# PolarGraph.net
KiCad netlist of a schematic drawn in Altium Designer
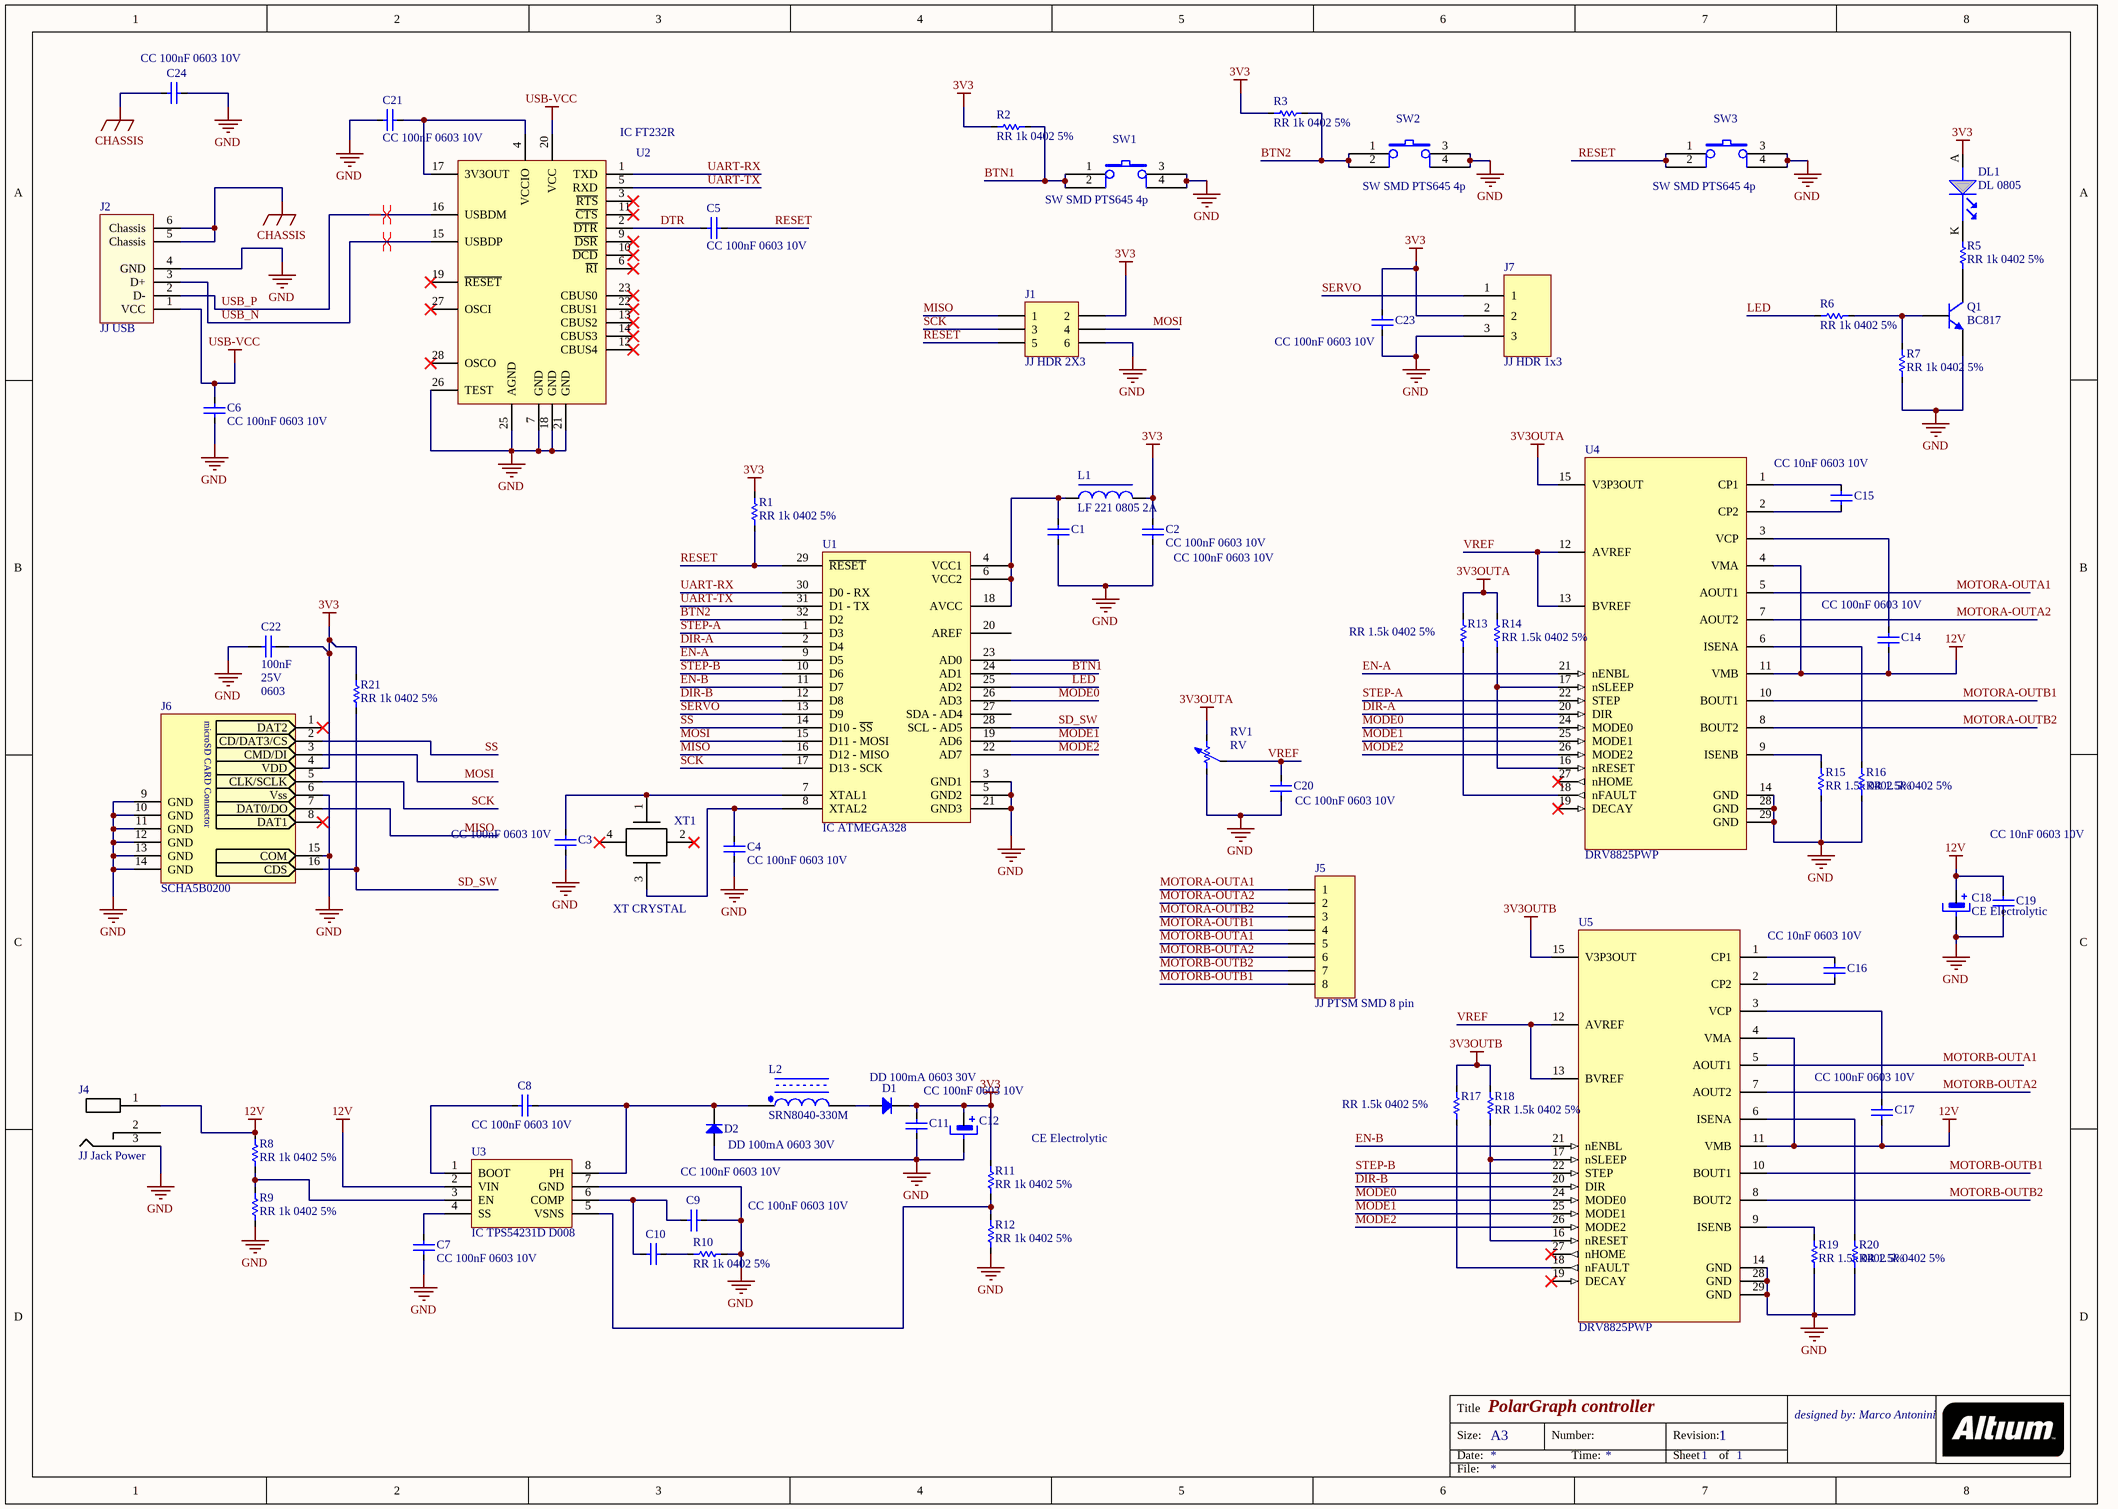
[diagram p0: PolarGraph.SchDoc]

(export (version "E")
  (design (tool "Eeschema 10.0.6"))
  (components
    (comp (ref "C1")
      (value "CC 100nF 0603 10V")
      (footprint "CC 0603 (1608 metric)")
      (description "Capacitor, Multi Layer Ceramic")
      (libsource (lib "ACME") (part "CC Ceramic"))
    )
    (comp (ref "C2")
      (value "CC 100nF 0603 10V")
      (footprint "CC 0603 (1608 metric)")
      (description "Capacitor, Multi Layer Ceramic")
      (libsource (lib "ACME") (part "CC Ceramic"))
    )
    (comp (ref "C3")
      (value "CC 100nF 0603 10V")
      (footprint "CC 0603 (1608 metric)")
      (description "Capacitor, Multi Layer Ceramic")
      (libsource (lib "ACME") (part "CC Ceramic"))
    )
    (comp (ref "C4")
      (value "CC 100nF 0603 10V")
      (footprint "CC 0603 (1608 metric)")
      (description "Capacitor, Multi Layer Ceramic")
      (libsource (lib "ACME") (part "CC Ceramic"))
    )
    (comp (ref "C5")
      (value "CC 100nF 0603 10V")
      (footprint "CC 0603 (1608 metric)")
      (description "Capacitor, Multi Layer Ceramic")
      (libsource (lib "ACME") (part "CC Ceramic"))
    )
    (comp (ref "C6")
      (value "CC 100nF 0603 10V")
      (footprint "CC 0603 (1608 metric)")
      (description "Capacitor, Multi Layer Ceramic")
      (libsource (lib "ACME") (part "CC Ceramic"))
    )
    (comp (ref "C7")
      (value "CC 100nF 0603 10V")
      (footprint "CC 0603 (1608 metric)")
      (description "Capacitor, Multi Layer Ceramic")
      (libsource (lib "ACME") (part "CC Ceramic"))
    )
    (comp (ref "C8")
      (value "CC 100nF 0603 10V")
      (footprint "CC 0603 (1608 metric)")
      (description "Capacitor, Multi Layer Ceramic")
      (libsource (lib "ACME") (part "CC Ceramic"))
    )
    (comp (ref "C9")
      (value "CC 100nF 0603 10V")
      (footprint "CC 0603 (1608 metric)")
      (description "Capacitor, Multi Layer Ceramic")
      (libsource (lib "ACME") (part "CC Ceramic"))
    )
    (comp (ref "C10")
      (value "CC 100nF 0603 10V")
      (footprint "CC 0603 (1608 metric)")
      (description "Capacitor, Multi Layer Ceramic")
      (libsource (lib "ACME") (part "CC Ceramic"))
    )
    (comp (ref "C11")
      (value "CC 100nF 0603 10V")
      (footprint "CC 0805 (2012 metric)")
      (description "Capacitor, Multi Layer Ceramic")
      (libsource (lib "ACME") (part "CC Ceramic"))
    )
    (comp (ref "C12")
      (value "CE Electrolytic")
      (footprint "CE 5.3x5.3x5.4")
      (description "Electrolytic Capacittor")
      (libsource (lib "ACME") (part "CE Electrolytic"))
    )
    (comp (ref "C14")
      (value "CC 100nF 0603 10V")
      (footprint "CC 0603 (1608 metric)")
      (description "Capacitor, Multi Layer Ceramic")
      (libsource (lib "ACME") (part "CC Ceramic"))
    )
    (comp (ref "C15")
      (value "CC 10nF 0603 10V")
      (footprint "CC 0603 (1608 metric)")
      (description "Capacitor, Multi Layer Ceramic")
      (libsource (lib "ACME") (part "CC Ceramic"))
    )
    (comp (ref "C16")
      (value "CC 10nF 0603 10V")
      (footprint "CC 0603 (1608 metric)")
      (description "Capacitor, Multi Layer Ceramic")
      (libsource (lib "ACME") (part "CC Ceramic"))
    )
    (comp (ref "C17")
      (value "CC 100nF 0603 10V")
      (footprint "CC 0603 (1608 metric)")
      (description "Capacitor, Multi Layer Ceramic")
      (libsource (lib "ACME") (part "CC Ceramic"))
    )
    (comp (ref "C18")
      (value "CE Electrolytic")
      (footprint "CE 6.6x6.6x5.4")
      (description "Electrolytic Capacittor")
      (libsource (lib "ACME") (part "CE Electrolytic"))
    )
    (comp (ref "C19")
      (value "CC 10nF 0603 10V")
      (footprint "CC 0805 (2012 metric)")
      (description "Capacitor, Multi Layer Ceramic")
      (libsource (lib "ACME") (part "CC Ceramic"))
    )
    (comp (ref "C20")
      (value "CC 100nF 0603 10V")
      (footprint "CC 0603 (1608 metric)")
      (description "Capacitor, Multi Layer Ceramic")
      (libsource (lib "ACME") (part "CC Ceramic"))
    )
    (comp (ref "C21")
      (value "CC 100nF 0603 10V")
      (footprint "CC 0603 (1608 metric)")
      (description "Capacitor, Multi Layer Ceramic")
      (libsource (lib "ACME") (part "CC Ceramic"))
    )
    (comp (ref "C22")
      (value "100nF")
      (footprint "0603_C")
      (description "Capacitor 0603, 100nF X7R 25V")
      (fields
        (field (name "VOLTAGE") "25V")
        (field (name "PACKAGE") "0603")
        (field (name "PART NUMBER") "C100nF-P0603-25V-X7R")
        (field (name "Comment") "Cap")
      )
      (libsource (lib "CROCO_DBLIB") (part "Cap"))
    )
    (comp (ref "C23")
      (value "CC 100nF 0603 10V")
      (footprint "CC 0805 (2012 metric)")
      (description "Capacitor, Multi Layer Ceramic")
      (libsource (lib "ACME") (part "CC Ceramic"))
    )
    (comp (ref "C24")
      (value "CC 100nF 0603 10V")
      (footprint "CC 1808 (4520 metric)")
      (description "Capacitor, Multi Layer Ceramic")
      (libsource (lib "ACME") (part "CC Ceramic"))
    )
    (comp (ref "D1")
      (value "DD 100mA 0603 30V")
      (footprint "DD SMA + SMB")
      (description "Normal Diode")
      (fields (field (name "PUBLISHER") "Altium Limited"))
      (libsource (lib "ACME") (part "DD Diode"))
    )
    (comp (ref "D2")
      (value "DD 100mA 0603 30V")
      (footprint "DD SMA + SMB")
      (description "Normal Diode")
      (fields (field (name "PUBLISHER") "Altium Limited"))
      (libsource (lib "ACME") (part "DD Diode"))
    )
    (comp (ref "DL1")
      (value "DL 0805")
      (footprint "LED 0805 - RED")
      (description "LED Diode 0805")
      (libsource (lib "Madefree") (part "DL Diode Led"))
    )
    (comp (ref "J1")
      (value "JJ HDR 2X3")
      (footprint "HDR 2X3")
      (libsource (lib "Madefree") (part "JJ HDR 2X3"))
    )
    (comp (ref "J2")
      (value "JJ USB")
      (footprint "USB Type B")
      (description "USB Socket")
      (libsource (lib "Madefree") (part "JJ USB"))
    )
    (comp (ref "J4")
      (value "JJ Jack Power")
      (footprint "JACK POWER")
      (libsource (lib "Madefree") (part "JJ Jack Power"))
    )
    (comp (ref "J5")
      (value "JJ PTSM SMD 8 pin")
      (footprint "PTSM 0,5/ 8-2,5-H SMD")
      (description "Terminal Block 8 pin")
      (fields (field (name "PUBLISHER") "Acme Systems"))
      (libsource (lib "Madefree") (part "JJ PTSM SMD 8 pin"))
    )
    (comp (ref "J6")
      (value "SCHA5B0200")
      (footprint "ALPS_SCHA5B0200")
      (description "microSD Card Connector (Push-push Type) SCHA Series")
      (fields (field (name "MANUFACTURER") "ALPS"))
      (libsource (lib "CROCO_DBLIB") (part "ALPS_SCHA5B0200"))
    )
    (comp (ref "J7")
      (value "JJ HDR 1x3")
      (footprint "HDR 1x3")
      (libsource (lib "Madefree") (part "JJ HDR 1x3"))
    )
    (comp (ref "L1")
      (value "LF 221 0805 2A")
      (footprint "LL 0603 (1608 metric)")
      (description "Ferrite 220 Ohm 2A 0805")
      (libsource (lib "ACME") (part "LF Ferrite"))
    )
    (comp (ref "L2")
      (value "SRN8040-330M")
      (footprint "INDC8080X400N")
      (description "Semi-shielded Power Inductors 33uH")
      (fields (field (name "MANUFACTURER") "Bourns"))
      (libsource (lib "CROCO_DBLIB") (part "INDUCTOR_SH"))
    )
    (comp (ref "Q1") (value "BC817") (footprint "SOT23_3") (libsource (lib "Madefree") (part "BC817")))
    (comp (ref "R1")
      (value "RR 1k 0402 5%")
      (footprint "RR 0603 (1608 metric)")
      (description "Resistor")
      (fields (field (name "PUBLISHER") "ACME Systems"))
      (libsource (lib "ACME") (part "RR Resistor"))
    )
    (comp (ref "R2")
      (value "RR 1k 0402 5%")
      (footprint "RR 0603 (1608 metric)")
      (description "Resistor")
      (fields (field (name "PUBLISHER") "ACME Systems"))
      (libsource (lib "ACME") (part "RR Resistor"))
    )
    (comp (ref "R3")
      (value "RR 1k 0402 5%")
      (footprint "RR 0603 (1608 metric)")
      (description "Resistor")
      (fields (field (name "PUBLISHER") "ACME Systems"))
      (libsource (lib "ACME") (part "RR Resistor"))
    )
    (comp (ref "R5")
      (value "RR 1k 0402 5%")
      (footprint "RR 0603 (1608 metric)")
      (description "Resistor")
      (fields (field (name "PUBLISHER") "ACME Systems"))
      (libsource (lib "ACME") (part "RR Resistor"))
    )
    (comp (ref "R6")
      (value "RR 1k 0402 5%")
      (footprint "RR 0603 (1608 metric)")
      (description "Resistor")
      (fields (field (name "PUBLISHER") "ACME Systems"))
      (libsource (lib "ACME") (part "RR Resistor"))
    )
    (comp (ref "R7")
      (value "RR 1k 0402 5%")
      (footprint "RR 0603 (1608 metric)")
      (description "Resistor")
      (fields (field (name "PUBLISHER") "ACME Systems"))
      (libsource (lib "ACME") (part "RR Resistor"))
    )
    (comp (ref "R8")
      (value "RR 1k 0402 5%")
      (footprint "RR 0603 (1608 metric)")
      (description "Resistor")
      (fields (field (name "PUBLISHER") "ACME Systems"))
      (libsource (lib "ACME") (part "RR Resistor"))
    )
    (comp (ref "R9")
      (value "RR 1k 0402 5%")
      (footprint "RR 0603 (1608 metric)")
      (description "Resistor")
      (fields (field (name "PUBLISHER") "ACME Systems"))
      (libsource (lib "ACME") (part "RR Resistor"))
    )
    (comp (ref "R10")
      (value "RR 1k 0402 5%")
      (footprint "RR 0603 (1608 metric)")
      (description "Resistor")
      (fields (field (name "PUBLISHER") "ACME Systems"))
      (libsource (lib "ACME") (part "RR Resistor"))
    )
    (comp (ref "R11")
      (value "RR 1k 0402 5%")
      (footprint "RR 0603 (1608 metric)")
      (description "Resistor")
      (fields (field (name "PUBLISHER") "ACME Systems"))
      (libsource (lib "ACME") (part "RR Resistor"))
    )
    (comp (ref "R12")
      (value "RR 1k 0402 5%")
      (footprint "RR 0603 (1608 metric)")
      (description "Resistor")
      (fields (field (name "PUBLISHER") "ACME Systems"))
      (libsource (lib "ACME") (part "RR Resistor"))
    )
    (comp (ref "R13")
      (value "RR 1.5k 0402 5%")
      (footprint "RR 0603 (1608 metric)")
      (description "Resistor")
      (fields (field (name "PUBLISHER") "ACME Systems"))
      (libsource (lib "ACME") (part "RR Resistor"))
    )
    (comp (ref "R14")
      (value "RR 1.5k 0402 5%")
      (footprint "RR 0603 (1608 metric)")
      (description "Resistor")
      (fields (field (name "PUBLISHER") "ACME Systems"))
      (libsource (lib "ACME") (part "RR Resistor"))
    )
    (comp (ref "R15")
      (value "RR 1.5k 0402 5%")
      (footprint "RR 0603 (1608 metric)")
      (description "Resistor")
      (fields (field (name "PUBLISHER") "ACME Systems"))
      (libsource (lib "ACME") (part "RR Resistor"))
    )
    (comp (ref "R16")
      (value "RR 1.5k 0402 5%")
      (footprint "RR 0603 (1608 metric)")
      (description "Resistor")
      (fields (field (name "PUBLISHER") "ACME Systems"))
      (libsource (lib "ACME") (part "RR Resistor"))
    )
    (comp (ref "R17")
      (value "RR 1.5k 0402 5%")
      (footprint "RR 0603 (1608 metric)")
      (description "Resistor")
      (fields (field (name "PUBLISHER") "ACME Systems"))
      (libsource (lib "ACME") (part "RR Resistor"))
    )
    (comp (ref "R18")
      (value "RR 1.5k 0402 5%")
      (footprint "RR 0603 (1608 metric)")
      (description "Resistor")
      (fields (field (name "PUBLISHER") "ACME Systems"))
      (libsource (lib "ACME") (part "RR Resistor"))
    )
    (comp (ref "R19")
      (value "RR 1.5k 0402 5%")
      (footprint "RR 0603 (1608 metric)")
      (description "Resistor")
      (fields (field (name "PUBLISHER") "ACME Systems"))
      (libsource (lib "ACME") (part "RR Resistor"))
    )
    (comp (ref "R20")
      (value "RR 1.5k 0402 5%")
      (footprint "RR 0603 (1608 metric)")
      (description "Resistor")
      (fields (field (name "PUBLISHER") "ACME Systems"))
      (libsource (lib "ACME") (part "RR Resistor"))
    )
    (comp (ref "R21")
      (value "RR 1k 0402 5%")
      (footprint "RR 0603 (1608 metric)")
      (description "Resistor")
      (fields (field (name "PUBLISHER") "ACME Systems"))
      (libsource (lib "ACME") (part "RR Resistor"))
    )
    (comp (ref "RV1")
      (value "RV")
      (footprint "RV ST-4EB")
      (description "Resistor")
      (fields (field (name "PUBLISHER") "ACME Systems"))
      (libsource (lib "ACME") (part "RV"))
    )
    (comp (ref "SW1")
      (value "SW SMD PTS645 4p")
      (footprint "Switch-4p PTS645")
      (description "Switch 4 pin PTS645")
      (libsource (lib "ACME") (part "SW SMD PTS645 4p"))
    )
    (comp (ref "SW2")
      (value "SW SMD PTS645 4p")
      (footprint "Switch-4p PTS645")
      (description "Switch 4 pin PTS645")
      (libsource (lib "ACME") (part "SW SMD PTS645 4p"))
    )
    (comp (ref "SW3")
      (value "SW SMD PTS645 4p")
      (footprint "Switch-4p PTS645")
      (description "Switch 4 pin PTS645")
      (libsource (lib "ACME") (part "SW SMD PTS645 4p"))
    )
    (comp (ref "U1")
      (value "IC ATMEGA328")
      (footprint "TQFP32")
      (libsource (lib "Madefree") (part "IC ATMEGA328"))
    )
    (comp (ref "U2")
      (value "IC FT232R")
      (footprint "SSOP28-FTDI")
      (description "The FT232BM is a USB to serial UART interface with the following advanced features")
      (libsource (lib "Madefree") (part "IC FT232R"))
    )
    (comp (ref "U3")
      (value "IC TPS54231D D008")
      (footprint "D008_M")
      (description "DC-DC converter TPS54231D D008")
      (fields (field (name "PUBLISHER") "Altium Limited"))
      (libsource (lib "ACME") (part "IC TPS54231D D008"))
    )
    (comp (ref "U4")
      (value "DRV8825PWP")
      (footprint "SOP65P640X120_HS-28N")
      (description "STEPPER MOTOR CONTROLLER IC")
      (fields (field (name "MANUFACTURER") "Texas Instrument"))
      (libsource (lib "CROCO_DBLIB") (part "DRV8825-28"))
    )
    (comp (ref "U5")
      (value "DRV8825PWP")
      (footprint "SOP65P640X120_HS-28N")
      (description "STEPPER MOTOR CONTROLLER IC")
      (fields (field (name "MANUFACTURER") "Texas Instrument"))
      (libsource (lib "CROCO_DBLIB") (part "DRV8825-28"))
    )
    (comp (ref "XT1")
      (value "XT CRYSTAL")
      (footprint "CRYSTAL 3.8x10.3")
      (libsource (lib "Madefree") (part "XT CRYSTAL"))
    )
  )
  (nets
    (net (code "1") (name "/BTN1") (class "Default")
      (node (ref "R2") (pin "1") (pinfunction "1_1") (pintype "passive"))
      (node (ref "SW1") (pin "1") (pinfunction "1_1") (pintype "passive"))
      (node (ref "SW1") (pin "2") (pinfunction "2_2") (pintype "passive"))
      (node (ref "U1") (pin "24") (pinfunction "AD1_24") (pintype "passive"))
    )
    (net (code "2") (name "/BTN2") (class "Default")
      (node (ref "R3") (pin "1") (pinfunction "1_1") (pintype "passive"))
      (node (ref "SW2") (pin "1") (pinfunction "1_1") (pintype "passive"))
      (node (ref "SW2") (pin "2") (pinfunction "2_2") (pintype "passive"))
      (node (ref "U1") (pin "32") (pinfunction "D2_32") (pintype "passive"))
    )
    (net (code "3") (name "/DIR-A") (class "Default")
      (node (ref "U1") (pin "2") (pinfunction "D4_2") (pintype "passive"))
      (node (ref "U4") (pin "20") (pinfunction "DIR_20") (pintype "input"))
    )
    (net (code "4") (name "/DIR-B") (class "Default")
      (node (ref "U1") (pin "12") (pinfunction "D8_12") (pintype "passive"))
      (node (ref "U5") (pin "20") (pinfunction "DIR_20") (pintype "input"))
    )
    (net (code "5") (name "/DTR") (class "Default")
      (node (ref "C5") (pin "1") (pinfunction "1_1") (pintype "passive"))
      (node (ref "U2") (pin "2") (pinfunction "~{DTR}_2") (pintype "passive"))
    )
    (net (code "6") (name "/EN-A") (class "Default")
      (node (ref "U1") (pin "9") (pinfunction "D5_9") (pintype "passive"))
      (node (ref "U4") (pin "21") (pinfunction "nENBL_21") (pintype "input"))
    )
    (net (code "7") (name "/EN-B") (class "Default")
      (node (ref "U1") (pin "11") (pinfunction "D7_11") (pintype "passive"))
      (node (ref "U5") (pin "21") (pinfunction "nENBL_21") (pintype "input"))
    )
    (net (code "8") (name "/LED") (class "Default")
      (node (ref "R6") (pin "1") (pinfunction "1_1") (pintype "passive"))
      (node (ref "U1") (pin "25") (pinfunction "AD2_25") (pintype "passive"))
    )
    (net (code "9") (name "/MISO") (class "Default")
      (node (ref "J1") (pin "1") (pinfunction "1_1") (pintype "passive"))
      (node (ref "J6") (pin "7") (pinfunction "DAT0/DO_7") (pintype "passive"))
      (node (ref "U1") (pin "16") (pinfunction "D12_-_MISO_16") (pintype "passive"))
    )
    (net (code "10") (name "/MODE0") (class "Default")
      (node (ref "U1") (pin "26") (pinfunction "AD3_26") (pintype "passive"))
      (node (ref "U4") (pin "24") (pinfunction "MODE0_24") (pintype "input"))
      (node (ref "U5") (pin "24") (pinfunction "MODE0_24") (pintype "input"))
    )
    (net (code "11") (name "/MODE1") (class "Default")
      (node (ref "U1") (pin "19") (pinfunction "AD6_19") (pintype "passive"))
      (node (ref "U4") (pin "25") (pinfunction "MODE1_25") (pintype "input"))
      (node (ref "U5") (pin "25") (pinfunction "MODE1_25") (pintype "input"))
    )
    (net (code "12") (name "/MODE2") (class "Default")
      (node (ref "U1") (pin "22") (pinfunction "AD7_22") (pintype "passive"))
      (node (ref "U4") (pin "26") (pinfunction "MODE2_26") (pintype "input"))
      (node (ref "U5") (pin "26") (pinfunction "MODE2_26") (pintype "input"))
    )
    (net (code "13") (name "/MOSI") (class "Default")
      (node (ref "J1") (pin "4") (pinfunction "4_4") (pintype "passive"))
      (node (ref "J6") (pin "3") (pinfunction "CMD/DI_3") (pintype "passive"))
      (node (ref "U1") (pin "15") (pinfunction "D11_-_MOSI_15") (pintype "passive"))
    )
    (net (code "14") (name "/MOTORA-OUTA1") (class "Default")
      (node (ref "J5") (pin "1") (pinfunction "1_1") (pintype "passive"))
      (node (ref "U4") (pin "5") (pinfunction "AOUT1_5") (pintype "passive"))
    )
    (net (code "15") (name "/MOTORA-OUTA2") (class "Default")
      (node (ref "J5") (pin "2") (pinfunction "2_2") (pintype "passive"))
      (node (ref "U4") (pin "7") (pinfunction "AOUT2_7") (pintype "passive"))
    )
    (net (code "16") (name "/MOTORA-OUTB1") (class "Default")
      (node (ref "J5") (pin "4") (pinfunction "4_4") (pintype "passive"))
      (node (ref "U4") (pin "10") (pinfunction "BOUT1_10") (pintype "passive"))
    )
    (net (code "17") (name "/MOTORA-OUTB2") (class "Default")
      (node (ref "J5") (pin "3") (pinfunction "3_3") (pintype "passive"))
      (node (ref "U4") (pin "8") (pinfunction "BOUT2_8") (pintype "passive"))
    )
    (net (code "18") (name "/MOTORB-OUTA1") (class "Default")
      (node (ref "J5") (pin "5") (pinfunction "5_5") (pintype "passive"))
      (node (ref "U5") (pin "5") (pinfunction "AOUT1_5") (pintype "passive"))
    )
    (net (code "19") (name "/MOTORB-OUTA2") (class "Default")
      (node (ref "J5") (pin "6") (pinfunction "6_6") (pintype "passive"))
      (node (ref "U5") (pin "7") (pinfunction "AOUT2_7") (pintype "passive"))
    )
    (net (code "20") (name "/MOTORB-OUTB1") (class "Default")
      (node (ref "J5") (pin "8") (pinfunction "8_8") (pintype "passive"))
      (node (ref "U5") (pin "10") (pinfunction "BOUT1_10") (pintype "passive"))
    )
    (net (code "21") (name "/MOTORB-OUTB2") (class "Default")
      (node (ref "J5") (pin "7") (pinfunction "7_7") (pintype "passive"))
      (node (ref "U5") (pin "8") (pinfunction "BOUT2_8") (pintype "passive"))
    )
    (net (code "22") (name "/RESET") (class "Default")
      (node (ref "C5") (pin "2") (pinfunction "2_2") (pintype "passive"))
      (node (ref "J1") (pin "5") (pinfunction "5_5") (pintype "passive"))
      (node (ref "R1") (pin "2") (pinfunction "2_2") (pintype "passive"))
      (node (ref "SW3") (pin "1") (pinfunction "1_1") (pintype "passive"))
      (node (ref "SW3") (pin "2") (pinfunction "2_2") (pintype "passive"))
      (node (ref "U1") (pin "29") (pinfunction "~{RESET}_29") (pintype "passive"))
    )
    (net (code "23") (name "/SCK") (class "Default")
      (node (ref "J1") (pin "3") (pinfunction "3_3") (pintype "passive"))
      (node (ref "J6") (pin "5") (pinfunction "CLK/SCLK_5") (pintype "passive"))
      (node (ref "U1") (pin "17") (pinfunction "D13_-_SCK_17") (pintype "passive"))
    )
    (net (code "24") (name "/SD_SW") (class "Default")
      (node (ref "J6") (pin "16") (pinfunction "CDS_16") (pintype "passive"))
      (node (ref "R21") (pin "2") (pinfunction "2_2") (pintype "passive"))
      (node (ref "U1") (pin "28") (pinfunction "SCL_-_AD5_28") (pintype "passive"))
    )
    (net (code "25") (name "/SERVO") (class "Default")
      (node (ref "J7") (pin "1") (pinfunction "1_1") (pintype "passive"))
      (node (ref "U1") (pin "13") (pinfunction "D9_13") (pintype "passive"))
    )
    (net (code "26") (name "/SS") (class "Default")
      (node (ref "J6") (pin "2") (pinfunction "CD/DAT3/CS_2") (pintype "passive"))
      (node (ref "U1") (pin "14") (pinfunction "D10_-_~{SS}_14") (pintype "passive"))
    )
    (net (code "27") (name "/STEP-A") (class "Default")
      (node (ref "U1") (pin "1") (pinfunction "D3_1") (pintype "passive"))
      (node (ref "U4") (pin "22") (pinfunction "STEP_22") (pintype "input"))
    )
    (net (code "28") (name "/STEP-B") (class "Default")
      (node (ref "U1") (pin "10") (pinfunction "D6_10") (pintype "passive"))
      (node (ref "U5") (pin "22") (pinfunction "STEP_22") (pintype "input"))
    )
    (net (code "29") (name "/UART-RX") (class "Default")
      (node (ref "U1") (pin "30") (pinfunction "D0_-_RX_30") (pintype "passive"))
      (node (ref "U2") (pin "1") (pinfunction "TXD_1") (pintype "passive"))
    )
    (net (code "30") (name "/UART-TX") (class "Default")
      (node (ref "U1") (pin "31") (pinfunction "D1_-_TX_31") (pintype "passive"))
      (node (ref "U2") (pin "5") (pinfunction "RXD_5") (pintype "passive"))
    )
    (net (code "31") (name "/USB_N") (class "Default")
      (node (ref "J2") (pin "3") (pinfunction "D+_3") (pintype "passive"))
      (node (ref "U2") (pin "15") (pinfunction "USBDP_15") (pintype "passive"))
    )
    (net (code "32") (name "/USB_P") (class "Default")
      (node (ref "J2") (pin "2") (pinfunction "D-_2") (pintype "passive"))
      (node (ref "U2") (pin "16") (pinfunction "USBDM_16") (pintype "passive"))
    )
    (net (code "33") (name "/VREF") (class "Default")
      (node (ref "C20") (pin "1") (pinfunction "1_1") (pintype "passive"))
      (node (ref "RV1") (pin "2") (pinfunction "2_2") (pintype "passive"))
      (node (ref "U4") (pin "12") (pinfunction "AVREF_12") (pintype "passive"))
      (node (ref "U4") (pin "13") (pinfunction "BVREF_13") (pintype "passive"))
      (node (ref "U5") (pin "12") (pinfunction "AVREF_12") (pintype "passive"))
      (node (ref "U5") (pin "13") (pinfunction "BVREF_13") (pintype "passive"))
    )
    (net (code "34") (name "3V3") (class "Default")
      (node (ref "C11") (pin "1") (pinfunction "1_1") (pintype "passive"))
      (node (ref "C12") (pin "1") (pinfunction "1_1") (pintype "passive"))
      (node (ref "C2") (pin "1") (pinfunction "1_1") (pintype "passive"))
      (node (ref "C22") (pin "2") (pinfunction "2_2") (pintype "passive"))
      (node (ref "C23") (pin "1") (pinfunction "1_1") (pintype "passive"))
      (node (ref "D1") (pin "K") (pinfunction "K_K") (pintype "passive"))
      (node (ref "DL1") (pin "A") (pinfunction "A_A") (pintype "passive"))
      (node (ref "J1") (pin "2") (pinfunction "2_2") (pintype "passive"))
      (node (ref "J6") (pin "4") (pinfunction "VDD_4") (pintype "passive"))
      (node (ref "J7") (pin "2") (pinfunction "2_2") (pintype "passive"))
      (node (ref "L1") (pin "2") (pinfunction "2_2") (pintype "passive"))
      (node (ref "R1") (pin "1") (pinfunction "1_1") (pintype "passive"))
      (node (ref "R11") (pin "2") (pinfunction "2_2") (pintype "passive"))
      (node (ref "R2") (pin "2") (pinfunction "2_2") (pintype "passive"))
      (node (ref "R21") (pin "1") (pinfunction "1_1") (pintype "passive"))
      (node (ref "R3") (pin "2") (pinfunction "2_2") (pintype "passive"))
    )
    (net (code "35") (name "3V3OUTA") (class "Default")
      (node (ref "R13") (pin "2") (pinfunction "2_2") (pintype "passive"))
      (node (ref "R14") (pin "2") (pinfunction "2_2") (pintype "passive"))
      (node (ref "RV1") (pin "3") (pinfunction "3_3") (pintype "passive"))
      (node (ref "U4") (pin "15") (pinfunction "V3P3OUT_15") (pintype "passive"))
    )
    (net (code "36") (name "3V3OUTB") (class "Default")
      (node (ref "R17") (pin "2") (pinfunction "2_2") (pintype "passive"))
      (node (ref "R18") (pin "2") (pinfunction "2_2") (pintype "passive"))
      (node (ref "U5") (pin "15") (pinfunction "V3P3OUT_15") (pintype "passive"))
    )
    (net (code "37") (name "12V") (class "Default")
      (node (ref "C14") (pin "1") (pinfunction "1_1") (pintype "passive"))
      (node (ref "C17") (pin "1") (pinfunction "1_1") (pintype "passive"))
      (node (ref "C18") (pin "1") (pinfunction "1_1") (pintype "passive"))
      (node (ref "C19") (pin "2") (pinfunction "2_2") (pintype "passive"))
      (node (ref "J4") (pin "1") (pinfunction "1_1") (pintype "passive"))
      (node (ref "R8") (pin "2") (pinfunction "2_2") (pintype "passive"))
      (node (ref "U3") (pin "2") (pinfunction "VIN_2") (pintype "passive"))
      (node (ref "U4") (pin "11") (pinfunction "VMB_11") (pintype "passive"))
      (node (ref "U4") (pin "4") (pinfunction "VMA_4") (pintype "passive"))
      (node (ref "U5") (pin "11") (pinfunction "VMB_11") (pintype "passive"))
      (node (ref "U5") (pin "4") (pinfunction "VMA_4") (pintype "passive"))
    )
    (net (code "38") (name "CHASSIS") (class "Default")
      (node (ref "C24") (pin "1") (pinfunction "1_1") (pintype "passive"))
      (node (ref "J2") (pin "5") (pinfunction "Chassis_5") (pintype "passive"))
      (node (ref "J2") (pin "6") (pinfunction "Chassis_6") (pintype "passive"))
    )
    (net (code "39") (name "GND") (class "Default")
      (node (ref "C1") (pin "2") (pinfunction "2_2") (pintype "passive"))
      (node (ref "C11") (pin "2") (pinfunction "2_2") (pintype "passive"))
      (node (ref "C12") (pin "2") (pinfunction "2_2") (pintype "passive"))
      (node (ref "C18") (pin "2") (pinfunction "2_2") (pintype "passive"))
      (node (ref "C19") (pin "1") (pinfunction "1_1") (pintype "passive"))
      (node (ref "C2") (pin "2") (pinfunction "2_2") (pintype "passive"))
      (node (ref "C20") (pin "2") (pinfunction "2_2") (pintype "passive"))
      (node (ref "C21") (pin "2") (pinfunction "2_2") (pintype "passive"))
      (node (ref "C22") (pin "1") (pinfunction "1_1") (pintype "passive"))
      (node (ref "C23") (pin "2") (pinfunction "2_2") (pintype "passive"))
      (node (ref "C24") (pin "2") (pinfunction "2_2") (pintype "passive"))
      (node (ref "C3") (pin "1") (pinfunction "1_1") (pintype "passive"))
      (node (ref "C4") (pin "1") (pinfunction "1_1") (pintype "passive"))
      (node (ref "C6") (pin "1") (pinfunction "1_1") (pintype "passive"))
      (node (ref "C7") (pin "2") (pinfunction "2_2") (pintype "passive"))
      (node (ref "C9") (pin "1") (pinfunction "1_1") (pintype "passive"))
      (node (ref "D2") (pin "A") (pinfunction "A_A") (pintype "passive"))
      (node (ref "J1") (pin "6") (pinfunction "6_6") (pintype "passive"))
      (node (ref "J2") (pin "4") (pinfunction "GND_4") (pintype "passive"))
      (node (ref "J4") (pin "3") (pinfunction "3_3") (pintype "passive"))
      (node (ref "J6") (pin "10") (pinfunction "GND_10") (pintype "passive"))
      (node (ref "J6") (pin "11") (pinfunction "GND_11") (pintype "passive"))
      (node (ref "J6") (pin "12") (pinfunction "GND_12") (pintype "passive"))
      (node (ref "J6") (pin "13") (pinfunction "GND_13") (pintype "passive"))
      (node (ref "J6") (pin "14") (pinfunction "GND_14") (pintype "passive"))
      (node (ref "J6") (pin "15") (pinfunction "COM_15") (pintype "passive"))
      (node (ref "J6") (pin "6") (pinfunction "Vss_6") (pintype "passive"))
      (node (ref "J6") (pin "9") (pinfunction "GND_9") (pintype "passive"))
      (node (ref "J7") (pin "3") (pinfunction "3_3") (pintype "passive"))
      (node (ref "Q1") (pin "2") (pinfunction "E_2") (pintype "passive"))
      (node (ref "R10") (pin "1") (pinfunction "1_1") (pintype "passive"))
      (node (ref "R12") (pin "1") (pinfunction "1_1") (pintype "passive"))
      (node (ref "R15") (pin "2") (pinfunction "2_2") (pintype "passive"))
      (node (ref "R16") (pin "2") (pinfunction "2_2") (pintype "passive"))
      (node (ref "R19") (pin "2") (pinfunction "2_2") (pintype "passive"))
      (node (ref "R20") (pin "2") (pinfunction "2_2") (pintype "passive"))
      (node (ref "R7") (pin "1") (pinfunction "1_1") (pintype "passive"))
      (node (ref "R9") (pin "1") (pinfunction "1_1") (pintype "passive"))
      (node (ref "RV1") (pin "1") (pinfunction "1_1") (pintype "passive"))
      (node (ref "SW1") (pin "3") (pinfunction "3_3") (pintype "passive"))
      (node (ref "SW1") (pin "4") (pinfunction "4_4") (pintype "passive"))
      (node (ref "SW2") (pin "3") (pinfunction "3_3") (pintype "passive"))
      (node (ref "SW2") (pin "4") (pinfunction "4_4") (pintype "passive"))
      (node (ref "SW3") (pin "3") (pinfunction "3_3") (pintype "passive"))
      (node (ref "SW3") (pin "4") (pinfunction "4_4") (pintype "passive"))
      (node (ref "U1") (pin "21") (pinfunction "GND3_21") (pintype "passive"))
      (node (ref "U1") (pin "3") (pinfunction "GND1_3") (pintype "passive"))
      (node (ref "U1") (pin "5") (pinfunction "GND2_5") (pintype "passive"))
      (node (ref "U2") (pin "18") (pinfunction "GND_18") (pintype "passive"))
      (node (ref "U2") (pin "21") (pinfunction "GND_21") (pintype "passive"))
      (node (ref "U2") (pin "25") (pinfunction "AGND_25") (pintype "passive"))
      (node (ref "U2") (pin "26") (pinfunction "TEST_26") (pintype "passive"))
      (node (ref "U2") (pin "7") (pinfunction "GND_7") (pintype "passive"))
      (node (ref "U3") (pin "7") (pinfunction "GND_7") (pintype "passive"))
      (node (ref "U4") (pin "14") (pinfunction "GND_14") (pintype "power_in"))
      (node (ref "U4") (pin "28") (pinfunction "GND_28") (pintype "power_in"))
      (node (ref "U4") (pin "29") (pinfunction "GND_29") (pintype "power_in"))
      (node (ref "U5") (pin "14") (pinfunction "GND_14") (pintype "power_in"))
      (node (ref "U5") (pin "28") (pinfunction "GND_28") (pintype "power_in"))
      (node (ref "U5") (pin "29") (pinfunction "GND_29") (pintype "power_in"))
    )
    (net (code "40") (name "Net-(C10-Pad1)") (class "Default")
      (node (ref "C10") (pin "1") (pinfunction "1_1") (pintype "passive"))
      (node (ref "R10") (pin "2") (pinfunction "2_2") (pintype "passive"))
    )
    (net (code "41") (name "Net-(D1-PadA)") (class "Default")
      (node (ref "D1") (pin "A") (pinfunction "A_A") (pintype "passive"))
      (node (ref "L2") (pin "2") (pinfunction "2_2") (pintype "passive"))
    )
    (net (code "42") (name "Net-(DL1-PadK)") (class "Default")
      (node (ref "DL1") (pin "K") (pinfunction "K_K") (pintype "passive"))
      (node (ref "R5") (pin "2") (pinfunction "2_2") (pintype "passive"))
    )
    (net (code "43") (name "Net-(Q1-B)") (class "Default")
      (node (ref "Q1") (pin "1") (pinfunction "B_1") (pintype "passive"))
      (node (ref "R6") (pin "2") (pinfunction "2_2") (pintype "passive"))
      (node (ref "R7") (pin "2") (pinfunction "2_2") (pintype "passive"))
    )
    (net (code "44") (name "Net-(Q1-C)") (class "Default")
      (node (ref "Q1") (pin "3") (pinfunction "C_3") (pintype "passive"))
      (node (ref "R5") (pin "1") (pinfunction "1_1") (pintype "passive"))
    )
    (net (code "45") (name "Net-(U1-AVCC)") (class "Default")
      (node (ref "C1") (pin "1") (pinfunction "1_1") (pintype "passive"))
      (node (ref "L1") (pin "1") (pinfunction "1_1") (pintype "passive"))
      (node (ref "U1") (pin "18") (pinfunction "AVCC_18") (pintype "passive"))
      (node (ref "U1") (pin "4") (pinfunction "VCC1_4") (pintype "passive"))
      (node (ref "U1") (pin "6") (pinfunction "VCC2_6") (pintype "passive"))
    )
    (net (code "46") (name "Net-(U1-XTAL1)") (class "Default")
      (node (ref "C3") (pin "2") (pinfunction "2_2") (pintype "passive"))
      (node (ref "U1") (pin "7") (pinfunction "XTAL1_7") (pintype "passive"))
      (node (ref "XT1") (pin "1") (pinfunction "X1_1") (pintype "passive"))
    )
    (net (code "47") (name "Net-(U1-XTAL2)") (class "Default")
      (node (ref "C4") (pin "2") (pinfunction "2_2") (pintype "passive"))
      (node (ref "U1") (pin "8") (pinfunction "XTAL2_8") (pintype "passive"))
      (node (ref "XT1") (pin "3") (pinfunction "X2_3") (pintype "passive"))
    )
    (net (code "48") (name "Net-(U2-3V3OUT)") (class "Default")
      (node (ref "C21") (pin "1") (pinfunction "1_1") (pintype "passive"))
      (node (ref "U2") (pin "17") (pinfunction "3V3OUT_17") (pintype "passive"))
      (node (ref "U2") (pin "4") (pinfunction "VCCIO_4") (pintype "passive"))
    )
    (net (code "49") (name "Net-(U3-BOOT)") (class "Default")
      (node (ref "C8") (pin "2") (pinfunction "2_2") (pintype "passive"))
      (node (ref "U3") (pin "1") (pinfunction "BOOT_1") (pintype "passive"))
    )
    (net (code "50") (name "Net-(U3-COMP)") (class "Default")
      (node (ref "C10") (pin "2") (pinfunction "2_2") (pintype "passive"))
      (node (ref "C9") (pin "2") (pinfunction "2_2") (pintype "passive"))
      (node (ref "U3") (pin "6") (pinfunction "COMP_6") (pintype "passive"))
    )
    (net (code "51") (name "Net-(U3-EN)") (class "Default")
      (node (ref "R8") (pin "1") (pinfunction "1_1") (pintype "passive"))
      (node (ref "R9") (pin "2") (pinfunction "2_2") (pintype "passive"))
      (node (ref "U3") (pin "3") (pinfunction "EN_3") (pintype "power_in"))
    )
    (net (code "52") (name "Net-(U3-PH)") (class "Default")
      (node (ref "C8") (pin "1") (pinfunction "1_1") (pintype "passive"))
      (node (ref "D2") (pin "K") (pinfunction "K_K") (pintype "passive"))
      (node (ref "L2") (pin "1") (pinfunction "1_1") (pintype "passive"))
      (node (ref "U3") (pin "8") (pinfunction "PH_8") (pintype "power_in"))
    )
    (net (code "53") (name "Net-(U3-SS)") (class "Default")
      (node (ref "C7") (pin "1") (pinfunction "1_1") (pintype "passive"))
      (node (ref "U3") (pin "4") (pinfunction "SS_4") (pintype "passive"))
    )
    (net (code "54") (name "Net-(U3-VSNS)") (class "Default")
      (node (ref "R11") (pin "1") (pinfunction "1_1") (pintype "passive"))
      (node (ref "R12") (pin "2") (pinfunction "2_2") (pintype "passive"))
      (node (ref "U3") (pin "5") (pinfunction "VSNS_5") (pintype "power_in"))
    )
    (net (code "55") (name "Net-(U4-CP1)") (class "Default")
      (node (ref "C15") (pin "2") (pinfunction "2_2") (pintype "passive"))
      (node (ref "U4") (pin "1") (pinfunction "CP1_1") (pintype "passive"))
    )
    (net (code "56") (name "Net-(U4-CP2)") (class "Default")
      (node (ref "C15") (pin "1") (pinfunction "1_1") (pintype "passive"))
      (node (ref "U4") (pin "2") (pinfunction "CP2_2") (pintype "passive"))
    )
    (net (code "57") (name "Net-(U4-ISENA)") (class "Default")
      (node (ref "R16") (pin "1") (pinfunction "1_1") (pintype "passive"))
      (node (ref "U4") (pin "6") (pinfunction "ISENA_6") (pintype "passive"))
    )
    (net (code "58") (name "Net-(U4-ISENB)") (class "Default")
      (node (ref "R15") (pin "1") (pinfunction "1_1") (pintype "passive"))
      (node (ref "U4") (pin "9") (pinfunction "ISENB_9") (pintype "passive"))
    )
    (net (code "59") (name "Net-(U4-VCP)") (class "Default")
      (node (ref "C14") (pin "2") (pinfunction "2_2") (pintype "passive"))
      (node (ref "U4") (pin "3") (pinfunction "VCP_3") (pintype "passive"))
    )
    (net (code "60") (name "Net-(U4-nFAULT)") (class "Default")
      (node (ref "R13") (pin "1") (pinfunction "1_1") (pintype "passive"))
      (node (ref "U4") (pin "18") (pinfunction "nFAULT_18") (pintype "output"))
    )
    (net (code "61") (name "Net-(U4-nRESET)") (class "Default")
      (node (ref "R14") (pin "1") (pinfunction "1_1") (pintype "passive"))
      (node (ref "U4") (pin "16") (pinfunction "nRESET_16") (pintype "input"))
      (node (ref "U4") (pin "17") (pinfunction "nSLEEP_17") (pintype "input"))
    )
    (net (code "62") (name "Net-(U5-CP1)") (class "Default")
      (node (ref "C16") (pin "2") (pinfunction "2_2") (pintype "passive"))
      (node (ref "U5") (pin "1") (pinfunction "CP1_1") (pintype "passive"))
    )
    (net (code "63") (name "Net-(U5-CP2)") (class "Default")
      (node (ref "C16") (pin "1") (pinfunction "1_1") (pintype "passive"))
      (node (ref "U5") (pin "2") (pinfunction "CP2_2") (pintype "passive"))
    )
    (net (code "64") (name "Net-(U5-ISENA)") (class "Default")
      (node (ref "R20") (pin "1") (pinfunction "1_1") (pintype "passive"))
      (node (ref "U5") (pin "6") (pinfunction "ISENA_6") (pintype "passive"))
    )
    (net (code "65") (name "Net-(U5-ISENB)") (class "Default")
      (node (ref "R19") (pin "1") (pinfunction "1_1") (pintype "passive"))
      (node (ref "U5") (pin "9") (pinfunction "ISENB_9") (pintype "passive"))
    )
    (net (code "66") (name "Net-(U5-VCP)") (class "Default")
      (node (ref "C17") (pin "2") (pinfunction "2_2") (pintype "passive"))
      (node (ref "U5") (pin "3") (pinfunction "VCP_3") (pintype "passive"))
    )
    (net (code "67") (name "Net-(U5-nFAULT)") (class "Default")
      (node (ref "R17") (pin "1") (pinfunction "1_1") (pintype "passive"))
      (node (ref "U5") (pin "18") (pinfunction "nFAULT_18") (pintype "output"))
    )
    (net (code "68") (name "Net-(U5-nRESET)") (class "Default")
      (node (ref "R18") (pin "1") (pinfunction "1_1") (pintype "passive"))
      (node (ref "U5") (pin "16") (pinfunction "nRESET_16") (pintype "input"))
      (node (ref "U5") (pin "17") (pinfunction "nSLEEP_17") (pintype "input"))
    )
    (net (code "69") (name "USB-VCC") (class "Default")
      (node (ref "C6") (pin "2") (pinfunction "2_2") (pintype "passive"))
      (node (ref "J2") (pin "1") (pinfunction "VCC_1") (pintype "passive"))
      (node (ref "U2") (pin "20") (pinfunction "VCC_20") (pintype "passive"))
    )
    (net (code "70") (name "unconnected-(J4-Pad2)") (class "Default")
      (node (ref "J4") (pin "2") (pinfunction "2_2") (pintype "passive"))
    )
    (net (code "71") (name "unconnected-(J6-DAT1-Pad8)") (class "Default")
      (node (ref "J6") (pin "8") (pinfunction "DAT1_8") (pintype "passive+no_connect"))
    )
    (net (code "72") (name "unconnected-(J6-DAT2-Pad1)") (class "Default")
      (node (ref "J6") (pin "1") (pinfunction "DAT2_1") (pintype "passive+no_connect"))
    )
    (net (code "73") (name "unconnected-(U1-AD0-Pad23)") (class "Default")
      (node (ref "U1") (pin "23") (pinfunction "AD0_23") (pintype "passive"))
    )
    (net (code "74") (name "unconnected-(U1-AREF-Pad20)") (class "Default")
      (node (ref "U1") (pin "20") (pinfunction "AREF_20") (pintype "passive"))
    )
    (net (code "75") (name "unconnected-(U1-SDA_-_AD4-Pad27)") (class "Default")
      (node (ref "U1") (pin "27") (pinfunction "SDA_-_AD4_27") (pintype "passive"))
    )
    (net (code "76") (name "unconnected-(U2-CBUS0-Pad23)") (class "Default")
      (node (ref "U2") (pin "23") (pinfunction "CBUS0_23") (pintype "passive+no_connect"))
    )
    (net (code "77") (name "unconnected-(U2-CBUS1-Pad22)") (class "Default")
      (node (ref "U2") (pin "22") (pinfunction "CBUS1_22") (pintype "passive+no_connect"))
    )
    (net (code "78") (name "unconnected-(U2-CBUS2-Pad13)") (class "Default")
      (node (ref "U2") (pin "13") (pinfunction "CBUS2_13") (pintype "passive+no_connect"))
    )
    (net (code "79") (name "unconnected-(U2-CBUS3-Pad14)") (class "Default")
      (node (ref "U2") (pin "14") (pinfunction "CBUS3_14") (pintype "passive+no_connect"))
    )
    (net (code "80") (name "unconnected-(U2-CBUS4-Pad12)") (class "Default")
      (node (ref "U2") (pin "12") (pinfunction "CBUS4_12") (pintype "passive+no_connect"))
    )
    (net (code "81") (name "unconnected-(U2-OSCI-Pad27)") (class "Default")
      (node (ref "U2") (pin "27") (pinfunction "OSCI_27") (pintype "passive+no_connect"))
    )
    (net (code "82") (name "unconnected-(U2-OSCO-Pad28)") (class "Default")
      (node (ref "U2") (pin "28") (pinfunction "OSCO_28") (pintype "passive+no_connect"))
    )
    (net (code "83") (name "unconnected-(U2-~{CTS}-Pad11)") (class "Default")
      (node (ref "U2") (pin "11") (pinfunction "~{CTS}_11") (pintype "passive+no_connect"))
    )
    (net (code "84") (name "unconnected-(U2-~{DCD}-Pad10)") (class "Default")
      (node (ref "U2") (pin "10") (pinfunction "~{DCD}_10") (pintype "passive+no_connect"))
    )
    (net (code "85") (name "unconnected-(U2-~{DSR}-Pad9)") (class "Default")
      (node (ref "U2") (pin "9") (pinfunction "~{DSR}_9") (pintype "passive+no_connect"))
    )
    (net (code "86") (name "unconnected-(U2-~{RESET}-Pad19)") (class "Default")
      (node (ref "U2") (pin "19") (pinfunction "~{RESET}_19") (pintype "passive+no_connect"))
    )
    (net (code "87") (name "unconnected-(U2-~{RI}-Pad6)") (class "Default")
      (node (ref "U2") (pin "6") (pinfunction "~{RI}_6") (pintype "passive+no_connect"))
    )
    (net (code "88") (name "unconnected-(U2-~{RTS}-Pad3)") (class "Default")
      (node (ref "U2") (pin "3") (pinfunction "~{RTS}_3") (pintype "passive+no_connect"))
    )
    (net (code "89") (name "unconnected-(U4-DECAY-Pad19)") (class "Default")
      (node (ref "U4") (pin "19") (pinfunction "DECAY_19") (pintype "input+no_connect"))
    )
    (net (code "90") (name "unconnected-(U4-nHOME-Pad27)") (class "Default")
      (node (ref "U4") (pin "27") (pinfunction "nHOME_27") (pintype "output+no_connect"))
    )
    (net (code "91") (name "unconnected-(U5-DECAY-Pad19)") (class "Default")
      (node (ref "U5") (pin "19") (pinfunction "DECAY_19") (pintype "input+no_connect"))
    )
    (net (code "92") (name "unconnected-(U5-nHOME-Pad27)") (class "Default")
      (node (ref "U5") (pin "27") (pinfunction "nHOME_27") (pintype "output+no_connect"))
    )
    (net (code "93") (name "unconnected-(XT1-GND-Pad2)") (class "Default")
      (node (ref "XT1") (pin "2") (pinfunction "GND_2") (pintype "passive+no_connect"))
    )
    (net (code "94") (name "unconnected-(XT1-GND-Pad4)") (class "Default")
      (node (ref "XT1") (pin "4") (pinfunction "GND_4") (pintype "passive+no_connect"))
    )
  )
)
